# ProPrj___20250317_2025-03-25.net
KiCad netlist of a schematic drawn in EasyEDA Pro
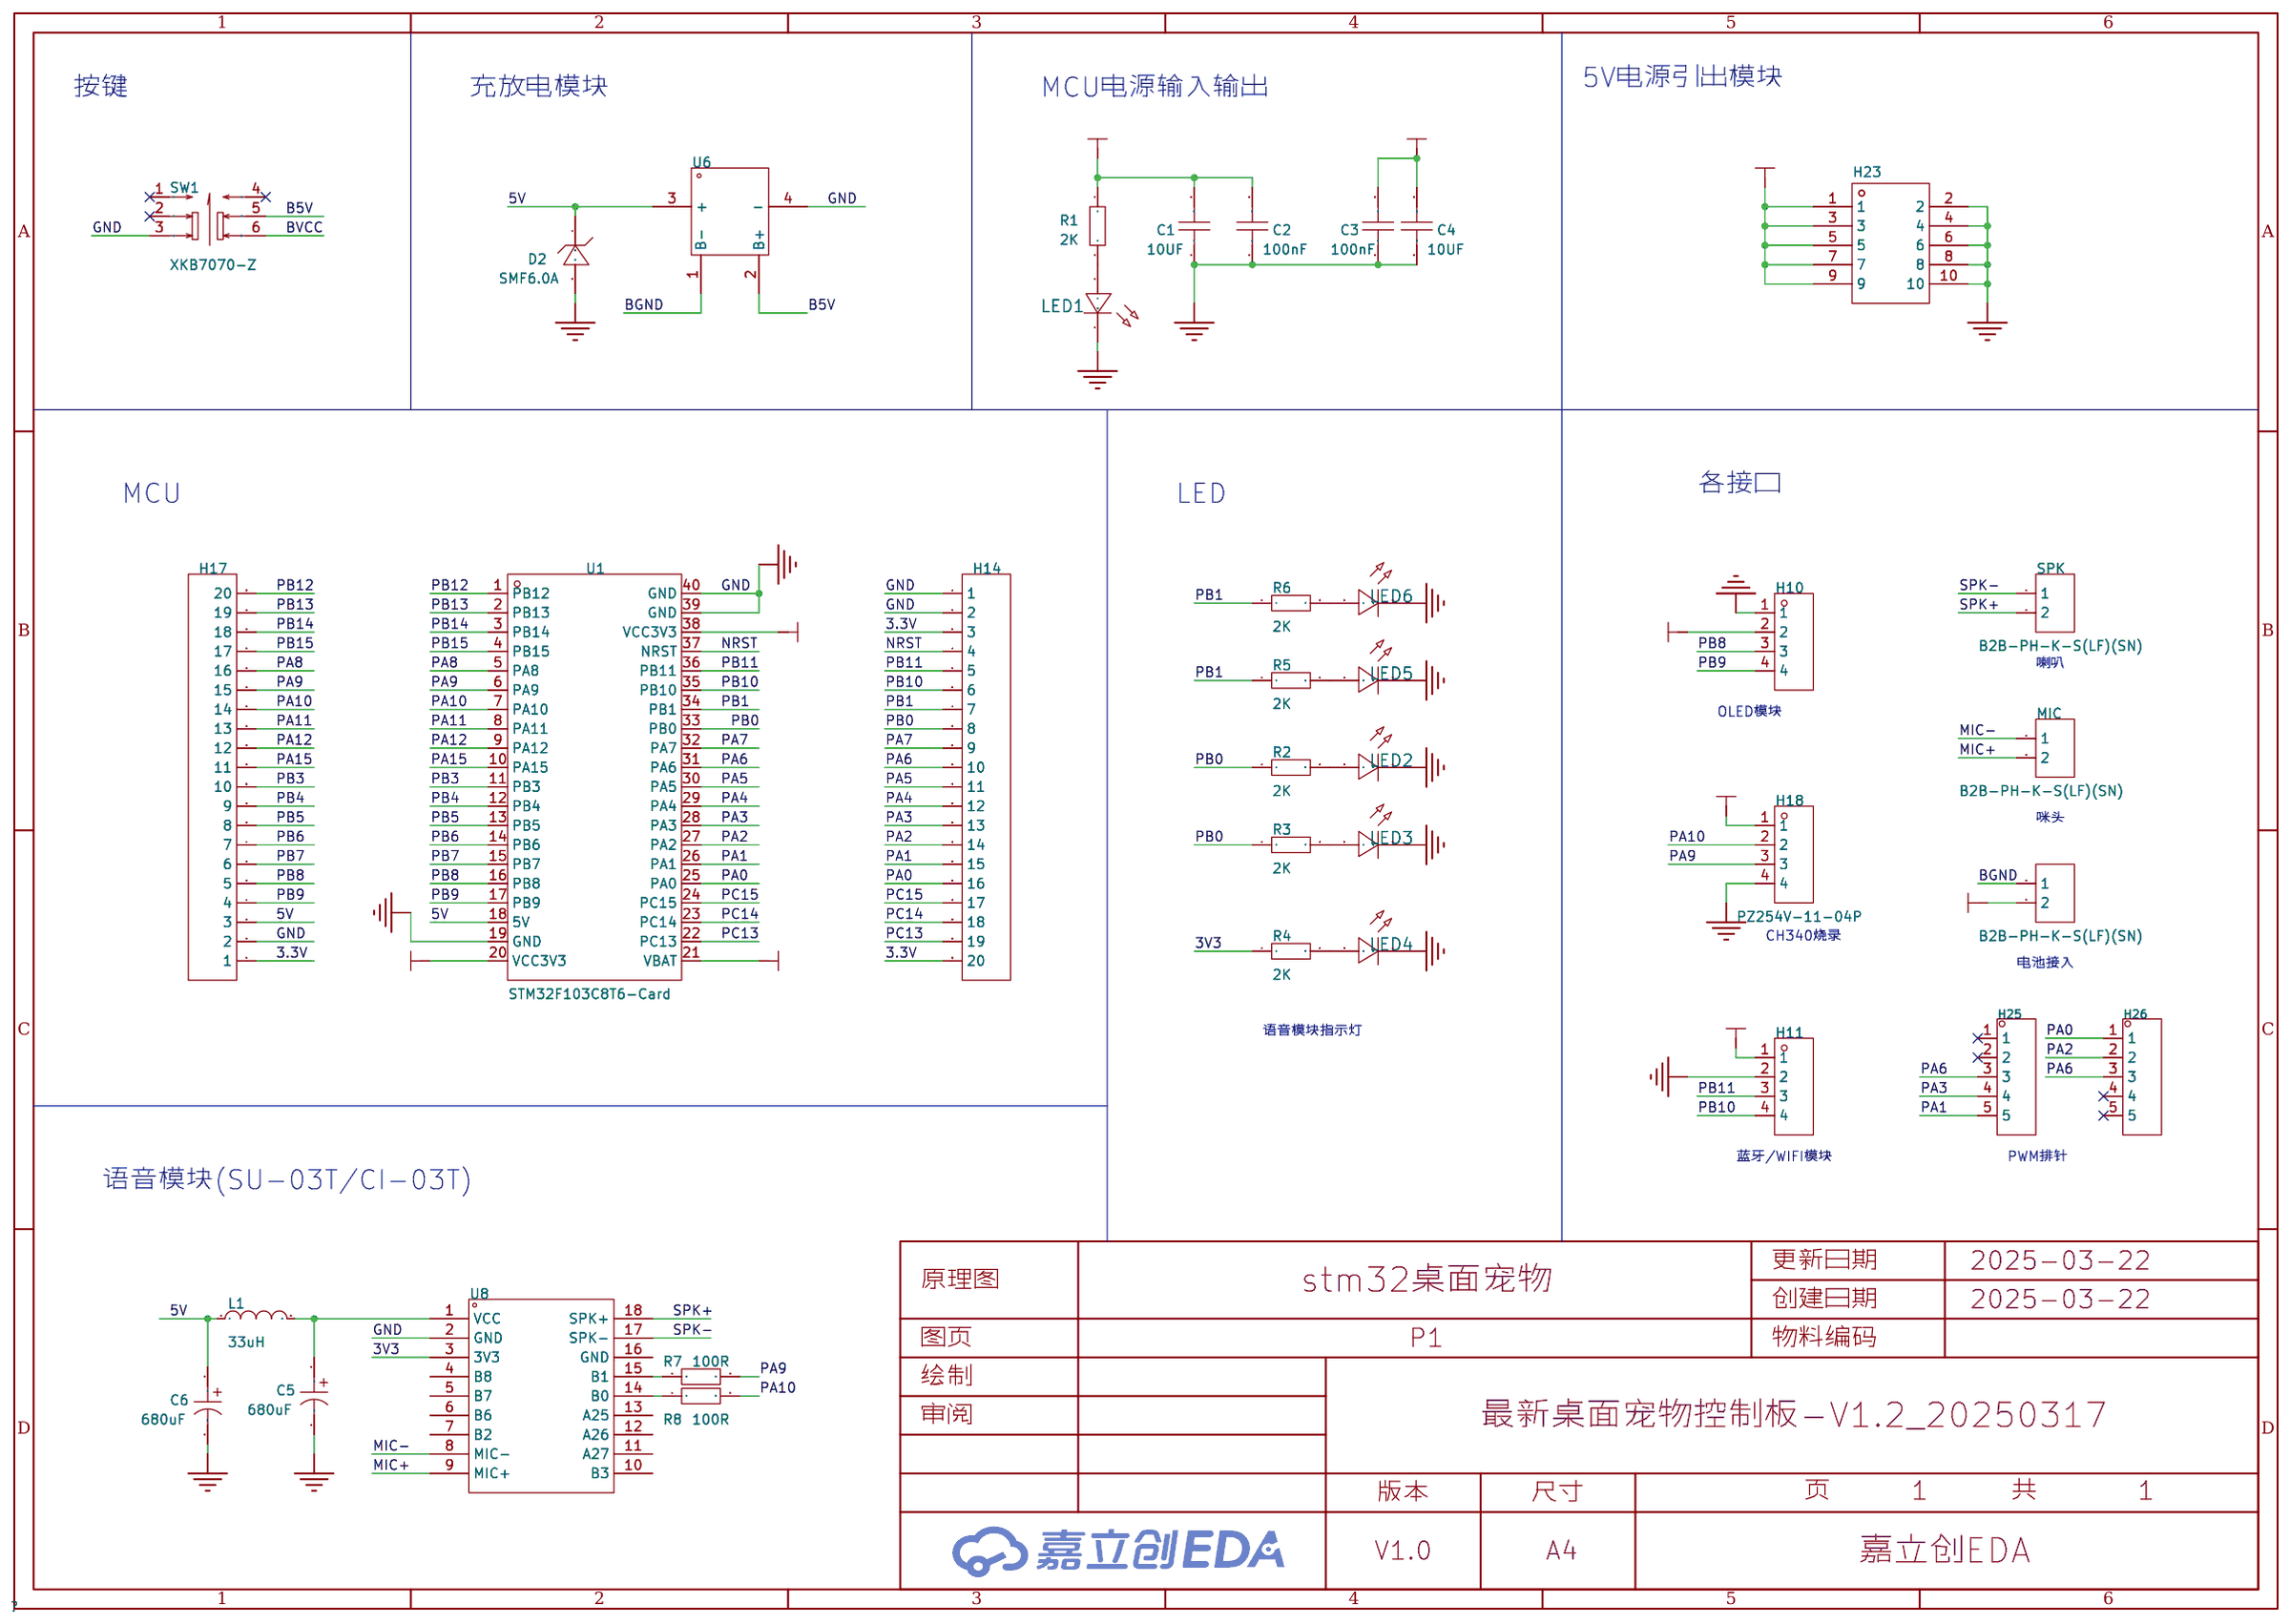
[diagram p0: schematic sheet]

(export (version "E")
  (design (tool "Eeschema 10.0.6"))
  (components
    (comp (ref "C1")
      (value "10UF")
      (footprint "easyedapro:C0805")
      (libsource (lib "easyedapro") (part "CapAcitance"))
    )
    (comp (ref "C2")
      (value "100nF")
      (footprint "easyedapro:C0805")
      (libsource (lib "easyedapro") (part "CapAcitance"))
    )
    (comp (ref "C3")
      (value "100nF")
      (footprint "easyedapro:C0805")
      (libsource (lib "easyedapro") (part "CapAcitance"))
    )
    (comp (ref "C4")
      (value "10UF")
      (footprint "easyedapro:C0805")
      (libsource (lib "easyedapro") (part "CapAcitance"))
    )
    (comp (ref "C5")
      (value "680uF")
      (footprint "easyedapro:CAP-TH_BD8.0-P3.50-D0.6-FD_1")
      (description "容值:470uF;额定电压:25V;")
      (fields
        (field (name "Manufacturer Part") "CD2884771EM0812VFL")
        (field (name "Manufacturer") "HRK(鸿瑞凯电子)")
      )
      (libsource (lib "easyedapro") (part "CD2884771EM0812VFL"))
    )
    (comp (ref "C6")
      (value "680uF")
      (footprint "easyedapro:CAP-TH_BD8.0-P3.50-D0.6-FD_1")
      (description "容值:470uF;额定电压:25V;")
      (fields
        (field (name "Manufacturer Part") "CD2884771EM0812VFL")
        (field (name "Manufacturer") "HRK(鸿瑞凯电子)")
      )
      (libsource (lib "easyedapro") (part "CD2884771EM0812VFL"))
    )
    (comp (ref "D2")
      (value "SMF6.0A")
      (footprint "easyedapro:SOD-123FL_L2.8-W1.8-LS3.8-RD")
      (description "极性:单向;反向截止电压(Vrwm):6V;钳位电压:10.3V;峰值脉冲电流(Ipp):19.4A;峰值脉冲功率(Ppp):200W;击穿电压:6.67V;")
      (fields (field (name "Manufacturer") "GOODWORK(固得沃克)"))
      (libsource (lib "easyedapro") (part "SMF6.0A_C2980406"))
    )
    (comp (ref "H10")
      (value "~")
      (footprint "easyedapro:HDR-TH_4P-P2.54-V-F")
      (libsource (lib "easyedapro") (part "2.54-1*4P母"))
    )
    (comp (ref "H11")
      (value "~")
      (footprint "easyedapro:HDR-TH_4P-P2.54-V-F")
      (libsource (lib "easyedapro") (part "2.54-1*4P母"))
    )
    (comp (ref "H14")
      (value "~")
      (footprint "easyedapro:HDR-TH_20P-P2.54-V-F")
      (libsource (lib "easyedapro") (part "HDR-F_2.54_1x20P"))
    )
    (comp (ref "H17")
      (value "~")
      (footprint "easyedapro:HDR-TH_20P-P2.54-V-F")
      (libsource (lib "easyedapro") (part "HDR-F_2.54_1x20P"))
    )
    (comp (ref "H18")
      (value "PZ254V-11-04P")
      (footprint "easyedapro:HDR-TH_4P-P2.54-V-F")
      (fields (field (name "Manufacturer") "XFCN(兴飞)"))
      (libsource (lib "easyedapro") (part "2.54-1*4P母"))
    )
    (comp (ref "H23")
      (value "~")
      (footprint "easyedapro:HDR-TH_10P-P2.54-V-M-R2-C5-S2.54")
      (libsource (lib "easyedapro") (part "HDR-M-2.54_2x5"))
    )
    (comp (ref "H25")
      (value "~")
      (footprint "easyedapro:HDR-TH_5P-P2.54-V-M")
      (libsource (lib "easyedapro") (part "MTP125-1105S1"))
    )
    (comp (ref "H26")
      (value "~")
      (footprint "easyedapro:HDR-TH_5P-P2.54-V-M")
      (libsource (lib "easyedapro") (part "MTP125-1105S1"))
    )
    (comp (ref "L1")
      (value "33uH")
      (footprint "easyedapro:IND-TH_BD7.5-P3.00-D0.6")
      (description "电感值:33uH;精度:±10%;饱和电流(Isat):1A;类型:磁环电感;")
      (fields (field (name "Manufacturer Part") "XR6*10-330K-S") (field (name "Manufacturer") "XR(祥如)"))
      (libsource (lib "easyedapro") (part "XR6*10-330K-S"))
    )
    (comp (ref "LED1")
      (value "~")
      (footprint "easyedapro:LED_0603")
      (libsource (lib "easyedapro") (part "LED_R"))
    )
    (comp (ref "LED2")
      (value "~")
      (footprint "easyedapro:LED_0603")
      (libsource (lib "easyedapro") (part "LED_R"))
    )
    (comp (ref "LED3")
      (value "~")
      (footprint "easyedapro:LED_0603")
      (libsource (lib "easyedapro") (part "LED_R"))
    )
    (comp (ref "LED4")
      (value "~")
      (footprint "easyedapro:LED_0603")
      (libsource (lib "easyedapro") (part "LED_R"))
    )
    (comp (ref "LED5")
      (value "~")
      (footprint "easyedapro:LED_0603")
      (libsource (lib "easyedapro") (part "LED_R"))
    )
    (comp (ref "LED6")
      (value "~")
      (footprint "easyedapro:LED_0603")
      (libsource (lib "easyedapro") (part "LED_R"))
    )
    (comp (ref "MIC")
      (value "B2B-PH-K-S(LF)(SN)")
      (footprint "easyedapro:HDR-TH_2P-P2.54-V-F")
      (fields (field (name "Manufacturer") "JST"))
      (libsource (lib "easyedapro") (part "Header-Female-2.54_1x2"))
    )
    (comp (ref "R1") (value "2K") (footprint "easyedapro:R0603") (libsource (lib "easyedapro") (part "电阻")))
    (comp (ref "R2") (value "2K") (footprint "easyedapro:R0603") (libsource (lib "easyedapro") (part "电阻")))
    (comp (ref "R3") (value "2K") (footprint "easyedapro:R0603") (libsource (lib "easyedapro") (part "电阻")))
    (comp (ref "R4") (value "2K") (footprint "easyedapro:R0603") (libsource (lib "easyedapro") (part "电阻")))
    (comp (ref "R5") (value "2K") (footprint "easyedapro:R0603") (libsource (lib "easyedapro") (part "电阻")))
    (comp (ref "R6") (value "2K") (footprint "easyedapro:R0603") (libsource (lib "easyedapro") (part "电阻")))
    (comp (ref "R7") (value "100R") (footprint "easyedapro:R0603") (libsource (lib "easyedapro") (part "电阻")))
    (comp (ref "R8") (value "100R") (footprint "easyedapro:R0603") (libsource (lib "easyedapro") (part "电阻")))
    (comp (ref "SPK")
      (value "B2B-PH-K-S(LF)(SN)")
      (footprint "easyedapro:HDR-TH_2P-P2.54-V-F")
      (fields (field (name "Manufacturer") "JST"))
      (libsource (lib "easyedapro") (part "Header-Female-2.54_1x2"))
    )
    (comp (ref "SW1")
      (value "XKB7070-Z")
      (footprint "easyedapro:SW-TH_6P-L7.0-W7.0-P2.00")
      (description "自锁/无锁:自锁;安装方式:直插;触点电流:100mA;额定电压 (AC):250V;额定电压 (DC):30V;带灯:不带;作用力:160gf;机械寿命:10万次;")
      (fields (field (name "Manufacturer") "XKB Connectivity(中国星坤)"))
      (libsource (lib "easyedapro") (part "XKB7070-Z"))
    )
    (comp (ref "U1")
      (value "STM32F103C8T6-Card")
      (footprint "easyedapro:CONN-TH_L53.3-W22.9_STM32F103C8T6-CARD")
      (libsource (lib "easyedapro") (part "STM32F103C8T6-CARD"))
    )
    (comp (ref "U6") (value "~") (libsource (lib "easyedapro") (part "5V充放电模块")))
    (comp (ref "U8")
      (value "~")
      (footprint "easyedapro:SU-03T带排针")
      (libsource (lib "easyedapro") (part "SU-03T带排针"))
    )
    (comp (ref "接锂电池")
      (value "B2B-PH-K-S(LF)(SN)")
      (footprint "easyedapro:HDR-TH_2P-P2.54-V-F")
      (fields (field (name "Manufacturer") "JST"))
      (libsource (lib "easyedapro") (part "Header-Female-2.54_1x2"))
    )
  )
  (nets
    (net (code "1") (name "/3V3") (class "Default")
      (node (ref "R4") (pin "1") (pinfunction "1_1") (pintype "input"))
      (node (ref "U8") (pin "3") (pinfunction "3V3_3") (pintype "input"))
    )
    (net (code "2") (name "/B5V") (class "Default")
      (node (ref "SW1") (pin "5") (pinfunction "5_5") (pintype "unspecified"))
      (node (ref "U6") (pin "2") (pinfunction "B+_2") (pintype "input"))
    )
    (net (code "3") (name "/BGND") (class "Default")
      (node (ref "U6") (pin "1") (pinfunction "B-_1") (pintype "input"))
      (node (ref "接锂电池") (pin "1") (pinfunction "1_1") (pintype "input"))
    )
    (net (code "4") (name "/MIC+") (class "Default")
      (node (ref "MIC") (pin "2") (pinfunction "2_2") (pintype "input"))
      (node (ref "U8") (pin "9") (pinfunction "MIC+_9") (pintype "input"))
    )
    (net (code "5") (name "/MIC-") (class "Default")
      (node (ref "MIC") (pin "1") (pinfunction "1_1") (pintype "input"))
      (node (ref "U8") (pin "8") (pinfunction "MIC-_8") (pintype "input"))
    )
    (net (code "6") (name "/NRST") (class "Default")
      (node (ref "H14") (pin "4") (pinfunction "4_4") (pintype "input"))
      (node (ref "U1") (pin "37") (pinfunction "NRST_37") (pintype "unspecified"))
    )
    (net (code "7") (name "/PA0") (class "Default")
      (node (ref "H14") (pin "16") (pinfunction "16_16") (pintype "input"))
      (node (ref "H26") (pin "1") (pinfunction "1_1") (pintype "input"))
      (node (ref "U1") (pin "25") (pinfunction "PA0_25") (pintype "unspecified"))
    )
    (net (code "8") (name "/PA1") (class "Default")
      (node (ref "H14") (pin "15") (pinfunction "15_15") (pintype "input"))
      (node (ref "H25") (pin "5") (pinfunction "5_5") (pintype "input"))
      (node (ref "U1") (pin "26") (pinfunction "PA1_26") (pintype "unspecified"))
    )
    (net (code "9") (name "/PA2") (class "Default")
      (node (ref "H14") (pin "14") (pinfunction "14_14") (pintype "input"))
      (node (ref "H26") (pin "2") (pinfunction "2_2") (pintype "input"))
      (node (ref "U1") (pin "27") (pinfunction "PA2_27") (pintype "unspecified"))
    )
    (net (code "10") (name "/PA3") (class "Default")
      (node (ref "H14") (pin "13") (pinfunction "13_13") (pintype "input"))
      (node (ref "H25") (pin "4") (pinfunction "4_4") (pintype "input"))
      (node (ref "U1") (pin "28") (pinfunction "PA3_28") (pintype "unspecified"))
    )
    (net (code "11") (name "/PA4") (class "Default")
      (node (ref "H14") (pin "12") (pinfunction "12_12") (pintype "input"))
      (node (ref "U1") (pin "29") (pinfunction "PA4_29") (pintype "unspecified"))
    )
    (net (code "12") (name "/PA5") (class "Default")
      (node (ref "H14") (pin "11") (pinfunction "11_11") (pintype "input"))
      (node (ref "U1") (pin "30") (pinfunction "PA5_30") (pintype "unspecified"))
    )
    (net (code "13") (name "/PA6") (class "Default")
      (node (ref "H14") (pin "10") (pinfunction "10_10") (pintype "input"))
      (node (ref "H25") (pin "3") (pinfunction "3_3") (pintype "input"))
      (node (ref "H26") (pin "3") (pinfunction "3_3") (pintype "input"))
      (node (ref "U1") (pin "31") (pinfunction "PA6_31") (pintype "unspecified"))
    )
    (net (code "14") (name "/PA7") (class "Default")
      (node (ref "H14") (pin "9") (pinfunction "9_9") (pintype "input"))
      (node (ref "U1") (pin "32") (pinfunction "PA7_32") (pintype "unspecified"))
    )
    (net (code "15") (name "/PA8") (class "Default")
      (node (ref "H17") (pin "16") (pinfunction "16_16") (pintype "input"))
      (node (ref "U1") (pin "5") (pinfunction "PA8_5") (pintype "unspecified"))
    )
    (net (code "16") (name "/PA9") (class "Default")
      (node (ref "H17") (pin "15") (pinfunction "15_15") (pintype "input"))
      (node (ref "H18") (pin "3") (pinfunction "3_3") (pintype "unspecified"))
      (node (ref "R7") (pin "2") (pinfunction "2_2") (pintype "input"))
      (node (ref "U1") (pin "6") (pinfunction "PA9_6") (pintype "unspecified"))
    )
    (net (code "17") (name "/PA10") (class "Default")
      (node (ref "H17") (pin "14") (pinfunction "14_14") (pintype "input"))
      (node (ref "H18") (pin "2") (pinfunction "2_2") (pintype "unspecified"))
      (node (ref "R8") (pin "2") (pinfunction "2_2") (pintype "input"))
      (node (ref "U1") (pin "7") (pinfunction "PA10_7") (pintype "unspecified"))
    )
    (net (code "18") (name "/PA11") (class "Default")
      (node (ref "H17") (pin "13") (pinfunction "13_13") (pintype "input"))
      (node (ref "U1") (pin "8") (pinfunction "PA11_8") (pintype "unspecified"))
    )
    (net (code "19") (name "/PA12") (class "Default")
      (node (ref "H17") (pin "12") (pinfunction "12_12") (pintype "input"))
      (node (ref "U1") (pin "9") (pinfunction "PA12_9") (pintype "unspecified"))
    )
    (net (code "20") (name "/PA15") (class "Default")
      (node (ref "H17") (pin "11") (pinfunction "11_11") (pintype "input"))
      (node (ref "U1") (pin "10") (pinfunction "PA15_10") (pintype "unspecified"))
    )
    (net (code "21") (name "/PB0") (class "Default")
      (node (ref "H14") (pin "8") (pinfunction "8_8") (pintype "input"))
      (node (ref "R2") (pin "1") (pinfunction "1_1") (pintype "input"))
      (node (ref "R3") (pin "1") (pinfunction "1_1") (pintype "input"))
      (node (ref "U1") (pin "33") (pinfunction "PB0_33") (pintype "unspecified"))
    )
    (net (code "22") (name "/PB1") (class "Default")
      (node (ref "H14") (pin "7") (pinfunction "7_7") (pintype "input"))
      (node (ref "R5") (pin "1") (pinfunction "1_1") (pintype "input"))
      (node (ref "R6") (pin "1") (pinfunction "1_1") (pintype "input"))
      (node (ref "U1") (pin "34") (pinfunction "PB1_34") (pintype "unspecified"))
    )
    (net (code "23") (name "/PB3") (class "Default")
      (node (ref "H17") (pin "10") (pinfunction "10_10") (pintype "input"))
      (node (ref "U1") (pin "11") (pinfunction "PB3_11") (pintype "unspecified"))
    )
    (net (code "24") (name "/PB4") (class "Default")
      (node (ref "H17") (pin "9") (pinfunction "9_9") (pintype "input"))
      (node (ref "U1") (pin "12") (pinfunction "PB4_12") (pintype "unspecified"))
    )
    (net (code "25") (name "/PB5") (class "Default")
      (node (ref "H17") (pin "8") (pinfunction "8_8") (pintype "input"))
      (node (ref "U1") (pin "13") (pinfunction "PB5_13") (pintype "unspecified"))
    )
    (net (code "26") (name "/PB6") (class "Default")
      (node (ref "H17") (pin "7") (pinfunction "7_7") (pintype "input"))
      (node (ref "U1") (pin "14") (pinfunction "PB6_14") (pintype "unspecified"))
    )
    (net (code "27") (name "/PB7") (class "Default")
      (node (ref "H17") (pin "6") (pinfunction "6_6") (pintype "input"))
      (node (ref "U1") (pin "15") (pinfunction "PB7_15") (pintype "unspecified"))
    )
    (net (code "28") (name "/PB8") (class "Default")
      (node (ref "H10") (pin "3") (pinfunction "3_3") (pintype "unspecified"))
      (node (ref "H17") (pin "5") (pinfunction "5_5") (pintype "input"))
      (node (ref "U1") (pin "16") (pinfunction "PB8_16") (pintype "unspecified"))
    )
    (net (code "29") (name "/PB9") (class "Default")
      (node (ref "H10") (pin "4") (pinfunction "4_4") (pintype "unspecified"))
      (node (ref "H17") (pin "4") (pinfunction "4_4") (pintype "input"))
      (node (ref "U1") (pin "17") (pinfunction "PB9_17") (pintype "unspecified"))
    )
    (net (code "30") (name "/PB10") (class "Default")
      (node (ref "H11") (pin "4") (pinfunction "4_4") (pintype "unspecified"))
      (node (ref "H14") (pin "6") (pinfunction "6_6") (pintype "input"))
      (node (ref "U1") (pin "35") (pinfunction "PB10_35") (pintype "unspecified"))
    )
    (net (code "31") (name "/PB11") (class "Default")
      (node (ref "H11") (pin "3") (pinfunction "3_3") (pintype "unspecified"))
      (node (ref "H14") (pin "5") (pinfunction "5_5") (pintype "input"))
      (node (ref "U1") (pin "36") (pinfunction "PB11_36") (pintype "unspecified"))
    )
    (net (code "32") (name "/PB12") (class "Default")
      (node (ref "H17") (pin "20") (pinfunction "20_20") (pintype "input"))
      (node (ref "U1") (pin "1") (pinfunction "PB12_1") (pintype "unspecified"))
    )
    (net (code "33") (name "/PB13") (class "Default")
      (node (ref "H17") (pin "19") (pinfunction "19_19") (pintype "input"))
      (node (ref "U1") (pin "2") (pinfunction "PB13_2") (pintype "unspecified"))
    )
    (net (code "34") (name "/PB14") (class "Default")
      (node (ref "H17") (pin "18") (pinfunction "18_18") (pintype "input"))
      (node (ref "U1") (pin "3") (pinfunction "PB14_3") (pintype "unspecified"))
    )
    (net (code "35") (name "/PB15") (class "Default")
      (node (ref "H17") (pin "17") (pinfunction "17_17") (pintype "input"))
      (node (ref "U1") (pin "4") (pinfunction "PB15_4") (pintype "unspecified"))
    )
    (net (code "36") (name "/PC13") (class "Default")
      (node (ref "H14") (pin "19") (pinfunction "19_19") (pintype "input"))
      (node (ref "U1") (pin "22") (pinfunction "PC13_22") (pintype "unspecified"))
    )
    (net (code "37") (name "/PC14") (class "Default")
      (node (ref "H14") (pin "18") (pinfunction "18_18") (pintype "input"))
      (node (ref "U1") (pin "23") (pinfunction "PC14_23") (pintype "unspecified"))
    )
    (net (code "38") (name "/PC15") (class "Default")
      (node (ref "H14") (pin "17") (pinfunction "17_17") (pintype "input"))
      (node (ref "U1") (pin "24") (pinfunction "PC15_24") (pintype "unspecified"))
    )
    (net (code "39") (name "/SPK+") (class "Default")
      (node (ref "SPK") (pin "2") (pinfunction "2_2") (pintype "input"))
      (node (ref "U8") (pin "18") (pinfunction "SPK+_18") (pintype "input"))
    )
    (net (code "40") (name "/SPK-") (class "Default")
      (node (ref "SPK") (pin "1") (pinfunction "1_1") (pintype "input"))
      (node (ref "U8") (pin "17") (pinfunction "SPK-_17") (pintype "input"))
    )
    (net (code "41") (name "3.3V") (class "Default")
      (node (ref "C3") (pin "2") (pinfunction "2_2") (pintype "input"))
      (node (ref "C4") (pin "2") (pinfunction "2_2") (pintype "input"))
      (node (ref "H10") (pin "2") (pinfunction "2_2") (pintype "unspecified"))
      (node (ref "H11") (pin "1") (pinfunction "1_1") (pintype "unspecified"))
      (node (ref "H14") (pin "20") (pinfunction "20_20") (pintype "input"))
      (node (ref "H14") (pin "3") (pinfunction "3_3") (pintype "input"))
      (node (ref "H17") (pin "1") (pinfunction "1_1") (pintype "input"))
      (node (ref "U1") (pin "20") (pinfunction "VCC3V3_20") (pintype "unspecified"))
      (node (ref "U1") (pin "21") (pinfunction "VBAT_21") (pintype "unspecified"))
      (node (ref "U1") (pin "38") (pinfunction "VCC3V3_38") (pintype "unspecified"))
    )
    (net (code "42") (name "5V") (class "Default")
      (node (ref "C1") (pin "2") (pinfunction "2_2") (pintype "input"))
      (node (ref "C2") (pin "2") (pinfunction "2_2") (pintype "input"))
      (node (ref "C6") (pin "1") (pinfunction "1_1") (pintype "input"))
      (node (ref "D2") (pin "1") (pinfunction "C_1") (pintype "unspecified"))
      (node (ref "H17") (pin "3") (pinfunction "3_3") (pintype "input"))
      (node (ref "H18") (pin "1") (pinfunction "1_1") (pintype "unspecified"))
      (node (ref "H23") (pin "1") (pinfunction "1_1") (pintype "input"))
      (node (ref "H23") (pin "3") (pinfunction "3_3") (pintype "input"))
      (node (ref "H23") (pin "5") (pinfunction "5_5") (pintype "input"))
      (node (ref "H23") (pin "7") (pinfunction "7_7") (pintype "input"))
      (node (ref "H23") (pin "9") (pinfunction "9_9") (pintype "input"))
      (node (ref "L1") (pin "1") (pinfunction "1_1") (pintype "unspecified"))
      (node (ref "R1") (pin "1") (pinfunction "1_1") (pintype "input"))
      (node (ref "U1") (pin "18") (pinfunction "5V_18") (pintype "unspecified"))
      (node (ref "U6") (pin "3") (pinfunction "+_3") (pintype "input"))
    )
    (net (code "43") (name "BVCC") (class "Default")
      (node (ref "SW1") (pin "6") (pinfunction "6_6") (pintype "unspecified"))
      (node (ref "接锂电池") (pin "2") (pinfunction "2_2") (pintype "input"))
    )
    (net (code "44") (name "GND") (class "Default")
      (node (ref "C1") (pin "1") (pinfunction "1_1") (pintype "input"))
      (node (ref "C2") (pin "1") (pinfunction "1_1") (pintype "input"))
      (node (ref "C3") (pin "1") (pinfunction "1_1") (pintype "input"))
      (node (ref "C4") (pin "1") (pinfunction "1_1") (pintype "input"))
      (node (ref "C5") (pin "2") (pinfunction "2_2") (pintype "input"))
      (node (ref "C6") (pin "2") (pinfunction "2_2") (pintype "input"))
      (node (ref "D2") (pin "2") (pinfunction "A_2") (pintype "unspecified"))
      (node (ref "H10") (pin "1") (pinfunction "1_1") (pintype "unspecified"))
      (node (ref "H11") (pin "2") (pinfunction "2_2") (pintype "unspecified"))
      (node (ref "H14") (pin "1") (pinfunction "1_1") (pintype "input"))
      (node (ref "H14") (pin "2") (pinfunction "2_2") (pintype "input"))
      (node (ref "H17") (pin "2") (pinfunction "2_2") (pintype "input"))
      (node (ref "H18") (pin "4") (pinfunction "4_4") (pintype "unspecified"))
      (node (ref "H23") (pin "10") (pinfunction "10_10") (pintype "input"))
      (node (ref "H23") (pin "2") (pinfunction "2_2") (pintype "input"))
      (node (ref "H23") (pin "4") (pinfunction "4_4") (pintype "input"))
      (node (ref "H23") (pin "6") (pinfunction "6_6") (pintype "input"))
      (node (ref "H23") (pin "8") (pinfunction "8_8") (pintype "input"))
      (node (ref "LED1") (pin "1") (pinfunction "C_1") (pintype "input"))
      (node (ref "LED2") (pin "1") (pinfunction "C_1") (pintype "input"))
      (node (ref "LED3") (pin "1") (pinfunction "C_1") (pintype "input"))
      (node (ref "LED4") (pin "1") (pinfunction "C_1") (pintype "input"))
      (node (ref "LED5") (pin "1") (pinfunction "C_1") (pintype "input"))
      (node (ref "LED6") (pin "1") (pinfunction "C_1") (pintype "input"))
      (node (ref "SW1") (pin "3") (pinfunction "3_3") (pintype "unspecified"))
      (node (ref "U1") (pin "19") (pinfunction "GND_19") (pintype "unspecified"))
      (node (ref "U1") (pin "39") (pinfunction "GND_39") (pintype "unspecified"))
      (node (ref "U1") (pin "40") (pinfunction "GND_40") (pintype "unspecified"))
      (node (ref "U6") (pin "4") (pinfunction "-_4") (pintype "input"))
      (node (ref "U8") (pin "2") (pinfunction "GND_2") (pintype "input"))
    )
    (net (code "45") (name "Net-(LED1-A)") (class "Default")
      (node (ref "LED1") (pin "2") (pinfunction "A_2") (pintype "input"))
      (node (ref "R1") (pin "2") (pinfunction "2_2") (pintype "input"))
    )
    (net (code "46") (name "Net-(LED2-A)") (class "Default")
      (node (ref "LED2") (pin "2") (pinfunction "A_2") (pintype "input"))
      (node (ref "R2") (pin "2") (pinfunction "2_2") (pintype "input"))
    )
    (net (code "47") (name "Net-(LED3-A)") (class "Default")
      (node (ref "LED3") (pin "2") (pinfunction "A_2") (pintype "input"))
      (node (ref "R3") (pin "2") (pinfunction "2_2") (pintype "input"))
    )
    (net (code "48") (name "Net-(LED4-A)") (class "Default")
      (node (ref "LED4") (pin "2") (pinfunction "A_2") (pintype "input"))
      (node (ref "R4") (pin "2") (pinfunction "2_2") (pintype "input"))
    )
    (net (code "49") (name "Net-(LED5-A)") (class "Default")
      (node (ref "LED5") (pin "2") (pinfunction "A_2") (pintype "input"))
      (node (ref "R5") (pin "2") (pinfunction "2_2") (pintype "input"))
    )
    (net (code "50") (name "Net-(LED6-A)") (class "Default")
      (node (ref "LED6") (pin "2") (pinfunction "A_2") (pintype "input"))
      (node (ref "R6") (pin "2") (pinfunction "2_2") (pintype "input"))
    )
    (net (code "51") (name "Net-(U8-B0)") (class "Default")
      (node (ref "R8") (pin "1") (pinfunction "1_1") (pintype "input"))
      (node (ref "U8") (pin "14") (pinfunction "B0_14") (pintype "input"))
    )
    (net (code "52") (name "Net-(U8-B1)") (class "Default")
      (node (ref "R7") (pin "1") (pinfunction "1_1") (pintype "input"))
      (node (ref "U8") (pin "15") (pinfunction "B1_15") (pintype "input"))
    )
    (net (code "53") (name "Net-(U8-VCC)") (class "Default")
      (node (ref "C5") (pin "1") (pinfunction "1_1") (pintype "input"))
      (node (ref "L1") (pin "2") (pinfunction "2_2") (pintype "unspecified"))
      (node (ref "U8") (pin "1") (pinfunction "VCC_1") (pintype "input"))
    )
    (net (code "54") (name "unconnected-(H25-Pad1)") (class "Default")
      (node (ref "H25") (pin "1") (pinfunction "1_1") (pintype "input+no_connect"))
    )
    (net (code "55") (name "unconnected-(H25-Pad2)") (class "Default")
      (node (ref "H25") (pin "2") (pinfunction "2_2") (pintype "input+no_connect"))
    )
    (net (code "56") (name "unconnected-(H26-Pad4)") (class "Default")
      (node (ref "H26") (pin "4") (pinfunction "4_4") (pintype "input+no_connect"))
    )
    (net (code "57") (name "unconnected-(H26-Pad5)") (class "Default")
      (node (ref "H26") (pin "5") (pinfunction "5_5") (pintype "input+no_connect"))
    )
    (net (code "58") (name "unconnected-(SW1-Pad1)") (class "Default")
      (node (ref "SW1") (pin "1") (pinfunction "1_1") (pintype "unspecified+no_connect"))
    )
    (net (code "59") (name "unconnected-(SW1-Pad2)") (class "Default")
      (node (ref "SW1") (pin "2") (pinfunction "2_2") (pintype "unspecified+no_connect"))
    )
    (net (code "60") (name "unconnected-(SW1-Pad4)") (class "Default")
      (node (ref "SW1") (pin "4") (pinfunction "4_4") (pintype "unspecified+no_connect"))
    )
    (net (code "61") (name "unconnected-(U8-A25-Pad13)") (class "Default")
      (node (ref "U8") (pin "13") (pinfunction "A25_13") (pintype "input"))
    )
    (net (code "62") (name "unconnected-(U8-A26-Pad12)") (class "Default")
      (node (ref "U8") (pin "12") (pinfunction "A26_12") (pintype "input"))
    )
    (net (code "63") (name "unconnected-(U8-A27-Pad11)") (class "Default")
      (node (ref "U8") (pin "11") (pinfunction "A27_11") (pintype "input"))
    )
    (net (code "64") (name "unconnected-(U8-B2-Pad7)") (class "Default")
      (node (ref "U8") (pin "7") (pinfunction "B2_7") (pintype "input"))
    )
    (net (code "65") (name "unconnected-(U8-B3-Pad10)") (class "Default")
      (node (ref "U8") (pin "10") (pinfunction "B3_10") (pintype "input"))
    )
    (net (code "66") (name "unconnected-(U8-B6-Pad6)") (class "Default")
      (node (ref "U8") (pin "6") (pinfunction "B6_6") (pintype "input"))
    )
    (net (code "67") (name "unconnected-(U8-B7-Pad5)") (class "Default")
      (node (ref "U8") (pin "5") (pinfunction "B7_5") (pintype "input"))
    )
    (net (code "68") (name "unconnected-(U8-B8-Pad4)") (class "Default")
      (node (ref "U8") (pin "4") (pinfunction "B8_4") (pintype "input"))
    )
    (net (code "69") (name "unconnected-(U8-GND-Pad16)") (class "Default")
      (node (ref "U8") (pin "16") (pinfunction "GND_16") (pintype "input"))
    )
  )
)
